# rc-filter.net
KiCad netlist of a schematic drawn in Altium Designer
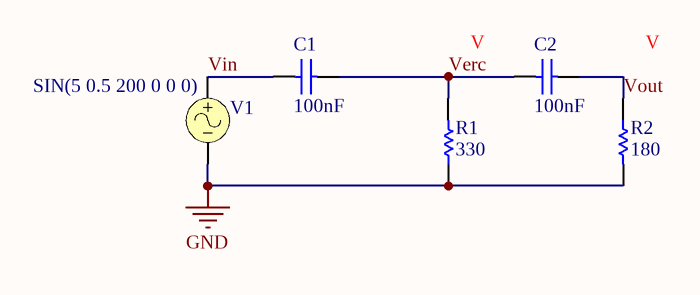
[diagram p0: rc-filter.SchDoc]

(export (version "E")
  (design (tool "Eeschema 10.0.6"))
  (components
    (comp (ref "C1")
      (value "100nF")
      (description "Capacitor")
      (libsource (lib "Simulation Generic Components") (part "Capacitor"))
    )
    (comp (ref "C2")
      (value "100nF")
      (description "Capacitor")
      (libsource (lib "Simulation Generic Components") (part "Capacitor"))
    )
    (comp (ref "R1")
      (value "330")
      (description "Resistor")
      (libsource (lib "Simulation Generic Components") (part "Resistor"))
    )
    (comp (ref "R2")
      (value "180")
      (description "Resistor")
      (libsource (lib "Simulation Generic Components") (part "Resistor"))
    )
    (comp (ref "V1")
      (value "SIN(5 0.5 200 0 0 0)")
      (description "Sinusoidal Voltage Source")
      (fields (field (name "PUBLISHER") "Altium Limited"))
      (libsource (lib "Simulation Generic Components") (part "VSIN"))
    )
  )
  (nets
    (net (code "1") (name "/Verc") (class "Default")
      (node (ref "C1") (pin "2") (pinfunction "2_2") (pintype "passive"))
      (node (ref "C2") (pin "1") (pinfunction "1_1") (pintype "passive"))
      (node (ref "R1") (pin "2") (pinfunction "2_2") (pintype "passive"))
    )
    (net (code "2") (name "/Vin") (class "Default")
      (node (ref "C1") (pin "1") (pinfunction "1_1") (pintype "passive"))
      (node (ref "V1") (pin "1") (pinfunction "1_1") (pintype "passive"))
    )
    (net (code "3") (name "/Vout") (class "Default")
      (node (ref "C2") (pin "2") (pinfunction "2_2") (pintype "passive"))
      (node (ref "R2") (pin "1") (pinfunction "1_1") (pintype "passive"))
    )
    (net (code "4") (name "GND") (class "Default")
      (node (ref "R1") (pin "1") (pinfunction "1_1") (pintype "passive"))
      (node (ref "R2") (pin "2") (pinfunction "2_2") (pintype "passive"))
      (node (ref "V1") (pin "2") (pinfunction "2_2") (pintype "passive"))
    )
  )
)
